# v6.net
KiCad netlist of a schematic drawn in EAGLE
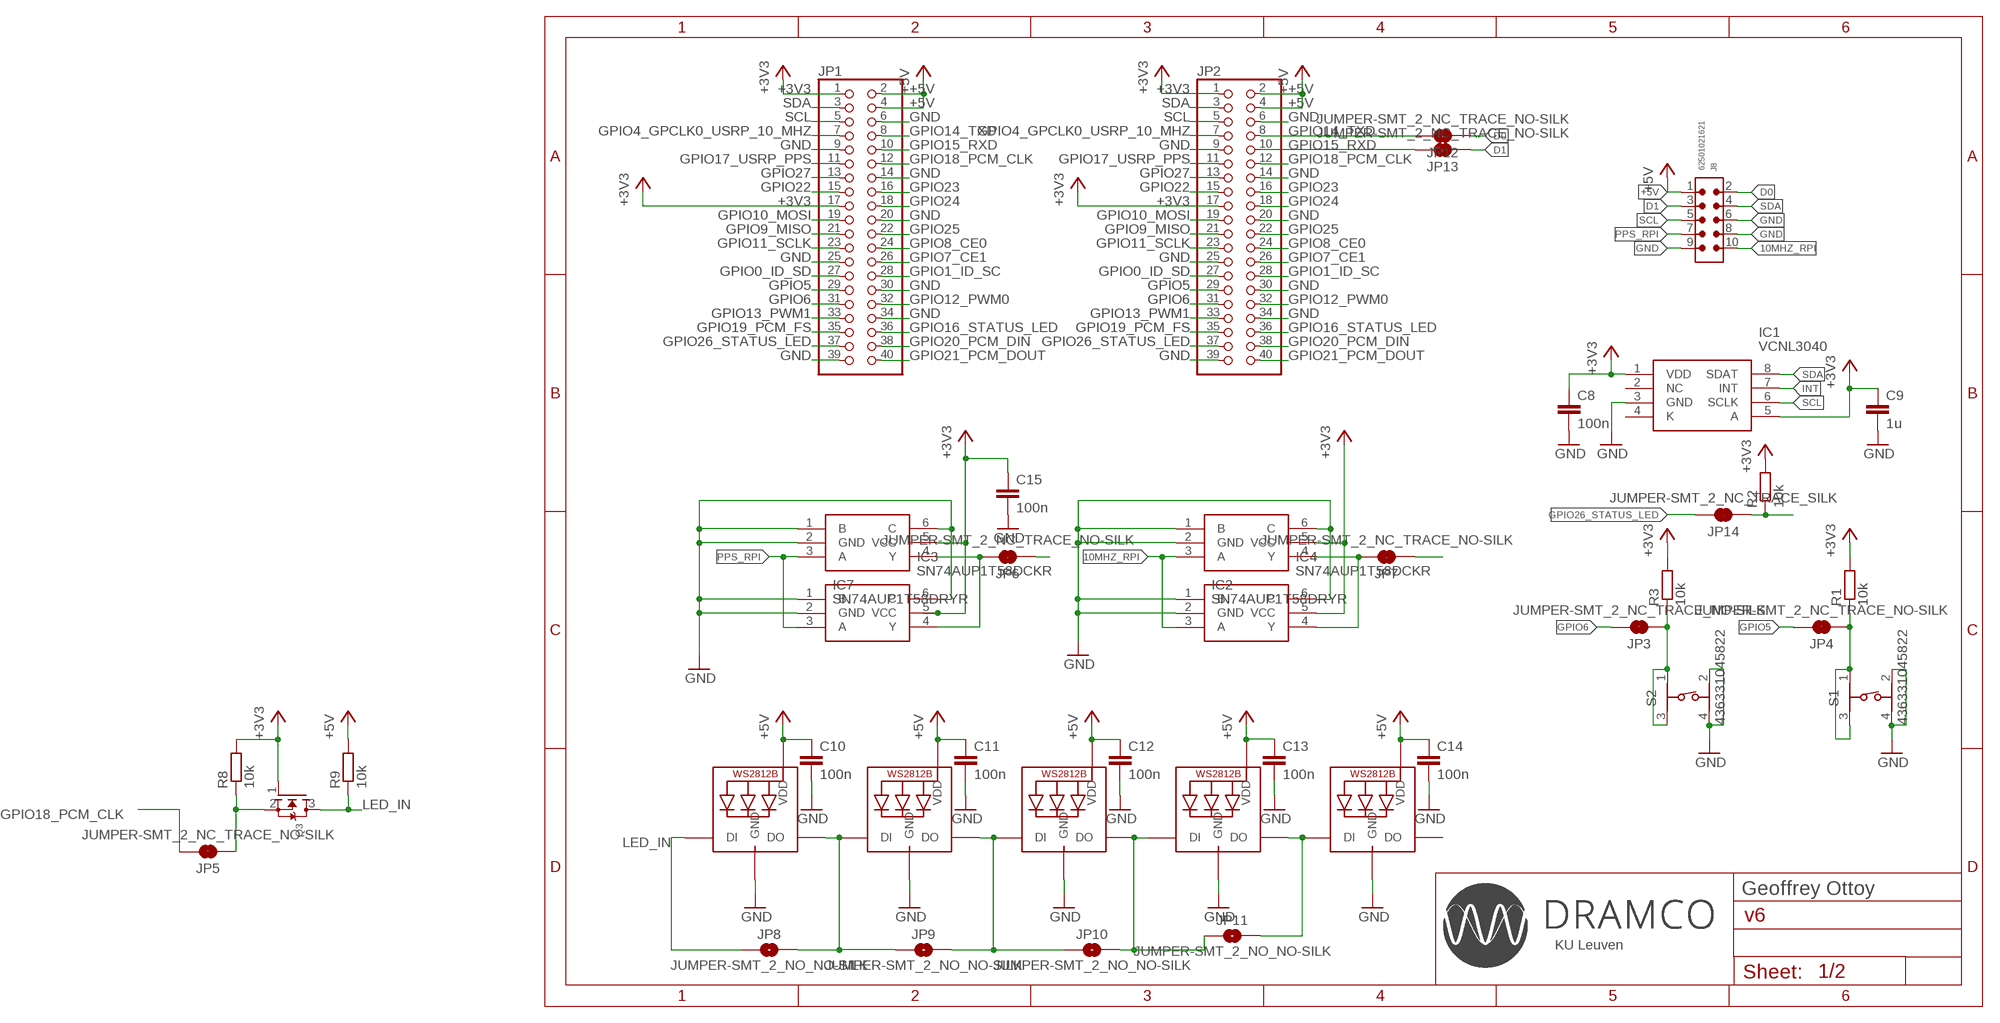
[diagram p0: schematic, sheet 1]
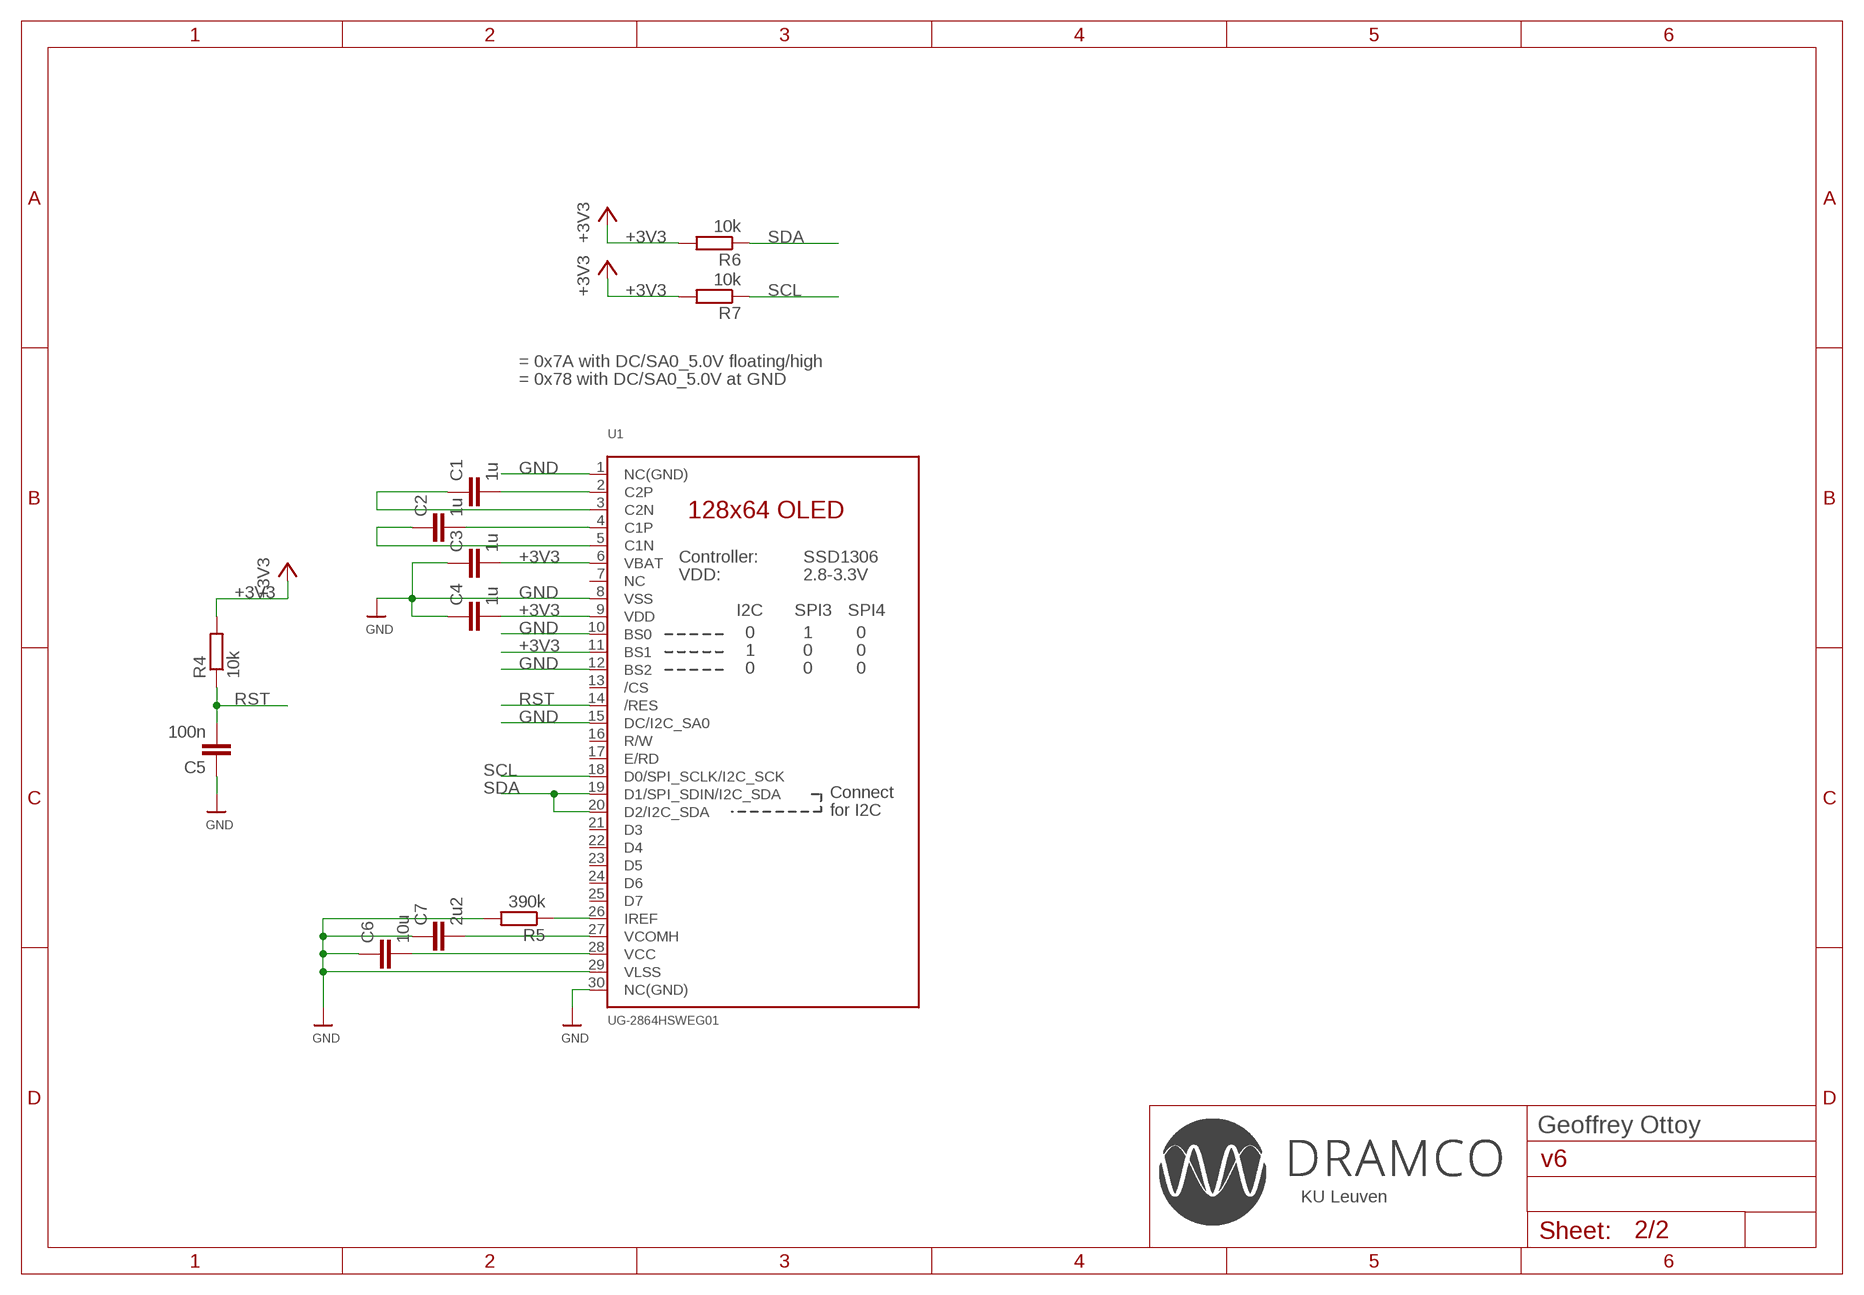
[diagram p1: schematic, sheet 2]

(export (version "E")
  (design (tool "Eeschema 10.0.6"))
  (components
    (comp (ref "C1")
      (value "1u")
      (footprint "eagle-import:C0603")
      (libsource (lib "eagle-import") (part "C-EUC0603"))
    )
    (comp (ref "C2")
      (value "1u")
      (footprint "eagle-import:C0603")
      (libsource (lib "eagle-import") (part "C-EUC0603"))
    )
    (comp (ref "C3")
      (value "1u")
      (footprint "eagle-import:C0603")
      (libsource (lib "eagle-import") (part "C-EUC0603"))
    )
    (comp (ref "C4")
      (value "1u")
      (footprint "eagle-import:C0603")
      (libsource (lib "eagle-import") (part "C-EUC0603"))
    )
    (comp (ref "C5")
      (value "100n")
      (footprint "eagle-import:C0603")
      (libsource (lib "eagle-import") (part "C-EUC0603"))
    )
    (comp (ref "C6")
      (value "10u")
      (footprint "eagle-import:C0603")
      (libsource (lib "eagle-import") (part "C-EUC0603"))
    )
    (comp (ref "C7")
      (value "2u2")
      (footprint "eagle-import:C0603")
      (libsource (lib "eagle-import") (part "C-EUC0603"))
    )
    (comp (ref "R4")
      (value "10k")
      (footprint "eagle-import:R0603")
      (libsource (lib "eagle-import") (part "R-EU_R0603"))
    )
    (comp (ref "R5")
      (value "390k")
      (footprint "eagle-import:R0603")
      (libsource (lib "eagle-import") (part "R-EU_R0603"))
    )
    (comp (ref "R6")
      (value "10k")
      (footprint "eagle-import:R0603")
      (libsource (lib "eagle-import") (part "R-EU_R0603"))
    )
    (comp (ref "R7")
      (value "10k")
      (footprint "eagle-import:R0603")
      (libsource (lib "eagle-import") (part "R-EU_R0603"))
    )
    (comp (ref "U1")
      (value "UG-2864HSWEG01")
      (footprint "eagle-import:UG-2864HSWEG01_0.96IN_WRAPAROUND")
      (libsource (lib "eagle-import") (part "DISP_OLED_UG-2864HSWEG010.96{dblquote}"))
    )
    (comp (ref "C8")
      (value "100n")
      (footprint "eagle-import:C0603")
      (libsource (lib "eagle-import") (part "C-EUC0603"))
    )
    (comp (ref "C9")
      (value "1u")
      (footprint "eagle-import:C0603")
      (libsource (lib "eagle-import") (part "C-EUC0603"))
    )
    (comp (ref "C10")
      (value "100n")
      (footprint "eagle-import:C0603")
      (libsource (lib "eagle-import") (part "C-EUC0603"))
    )
    (comp (ref "C11")
      (value "100n")
      (footprint "eagle-import:C0603")
      (libsource (lib "eagle-import") (part "C-EUC0603"))
    )
    (comp (ref "C12")
      (value "100n")
      (footprint "eagle-import:C0603")
      (libsource (lib "eagle-import") (part "C-EUC0603"))
    )
    (comp (ref "C13")
      (value "100n")
      (footprint "eagle-import:C0603")
      (libsource (lib "eagle-import") (part "C-EUC0603"))
    )
    (comp (ref "C14")
      (value "100n")
      (footprint "eagle-import:C0603")
      (libsource (lib "eagle-import") (part "C-EUC0603"))
    )
    (comp (ref "C15")
      (value "100n")
      (footprint "eagle-import:C0603")
      (libsource (lib "eagle-import") (part "C-EUC0603"))
    )
    (comp (ref "IC1")
      (value "VCNL3040")
      (footprint "eagle-import:SON108P200X400X115-8N")
      (fields (field (name "MOUSER_PART_NUMBER") "78-VCNL3040"))
      (libsource (lib "eagle-import") (part "VCNL3040"))
    )
    (comp (ref "IC2")
      (value "SN74AUP1T58DRYR")
      (footprint "eagle-import:SON50P100X145X60-6N")
      (libsource (lib "eagle-import") (part "SN74AUP1T58DRYR"))
    )
    (comp (ref "IC3")
      (value "SN74AUP1T58DCKR")
      (footprint "eagle-import:SOT65P210X110-6N")
      (libsource (lib "eagle-import") (part "SN74AUP1T58DCKR"))
    )
    (comp (ref "IC4")
      (value "SN74AUP1T58DCKR")
      (footprint "eagle-import:SOT65P210X110-6N")
      (libsource (lib "eagle-import") (part "SN74AUP1T58DCKR"))
    )
    (comp (ref "IC7")
      (value "SN74AUP1T58DRYR")
      (footprint "eagle-import:SON50P100X145X60-6N")
      (libsource (lib "eagle-import") (part "SN74AUP1T58DRYR"))
    )
    (comp (ref "J8")
      (value "62501021621")
      (footprint "eagle-import:62501021621")
      (libsource (lib "eagle-import") (part "6250XX21621_62501021621"))
    )
    (comp (ref "JP1")
      (value "PINHD-2X20")
      (footprint "eagle-import:2X20")
      (libsource (lib "eagle-import") (part "PINHD-2X20"))
    )
    (comp (ref "JP2")
      (value "PINHD-2X20/90")
      (footprint "eagle-import:2X20_90")
      (libsource (lib "eagle-import") (part "PINHD-2X20/90"))
    )
    (comp (ref "JP3")
      (value "JUMPER-SMT_2_NC_TRACE_NO-SILK")
      (footprint "eagle-import:SMT-JUMPER_2_NC_TRACE_NO-SILK")
      (libsource (lib "eagle-import") (part "JUMPER-SMT_2_NC_TRACE_NO-SILK"))
    )
    (comp (ref "JP4")
      (value "JUMPER-SMT_2_NC_TRACE_NO-SILK")
      (footprint "eagle-import:SMT-JUMPER_2_NC_TRACE_NO-SILK")
      (libsource (lib "eagle-import") (part "JUMPER-SMT_2_NC_TRACE_NO-SILK"))
    )
    (comp (ref "JP5")
      (value "JUMPER-SMT_2_NC_TRACE_NO-SILK")
      (footprint "eagle-import:SMT-JUMPER_2_NC_TRACE_NO-SILK")
      (libsource (lib "eagle-import") (part "JUMPER-SMT_2_NC_TRACE_NO-SILK"))
    )
    (comp (ref "JP6")
      (value "JUMPER-SMT_2_NC_TRACE_NO-SILK")
      (footprint "eagle-import:SMT-JUMPER_2_NC_TRACE_NO-SILK")
      (libsource (lib "eagle-import") (part "JUMPER-SMT_2_NC_TRACE_NO-SILK"))
    )
    (comp (ref "JP7")
      (value "JUMPER-SMT_2_NC_TRACE_NO-SILK")
      (footprint "eagle-import:SMT-JUMPER_2_NC_TRACE_NO-SILK")
      (libsource (lib "eagle-import") (part "JUMPER-SMT_2_NC_TRACE_NO-SILK"))
    )
    (comp (ref "JP8")
      (value "JUMPER-SMT_2_NO_NO-SILK")
      (footprint "eagle-import:SMT-JUMPER_2_NO_NO-SILK")
      (libsource (lib "eagle-import") (part "JUMPER-SMT_2_NO_NO-SILK"))
    )
    (comp (ref "JP9")
      (value "JUMPER-SMT_2_NO_NO-SILK")
      (footprint "eagle-import:SMT-JUMPER_2_NO_NO-SILK")
      (libsource (lib "eagle-import") (part "JUMPER-SMT_2_NO_NO-SILK"))
    )
    (comp (ref "JP10")
      (value "JUMPER-SMT_2_NO_NO-SILK")
      (footprint "eagle-import:SMT-JUMPER_2_NO_NO-SILK")
      (libsource (lib "eagle-import") (part "JUMPER-SMT_2_NO_NO-SILK"))
    )
    (comp (ref "JP11")
      (value "JUMPER-SMT_2_NO_NO-SILK")
      (footprint "eagle-import:SMT-JUMPER_2_NO_NO-SILK")
      (libsource (lib "eagle-import") (part "JUMPER-SMT_2_NO_NO-SILK"))
    )
    (comp (ref "JP12")
      (value "JUMPER-SMT_2_NC_TRACE_NO-SILK")
      (footprint "eagle-import:SMT-JUMPER_2_NC_TRACE_NO-SILK")
      (libsource (lib "eagle-import") (part "JUMPER-SMT_2_NC_TRACE_NO-SILK"))
    )
    (comp (ref "JP13")
      (value "JUMPER-SMT_2_NC_TRACE_NO-SILK")
      (footprint "eagle-import:SMT-JUMPER_2_NC_TRACE_NO-SILK")
      (libsource (lib "eagle-import") (part "JUMPER-SMT_2_NC_TRACE_NO-SILK"))
    )
    (comp (ref "JP14")
      (value "JUMPER-SMT_2_NC_TRACE_SILK")
      (footprint "eagle-import:SMT-JUMPER_2_NC_TRACE_SILK")
      (libsource (lib "eagle-import") (part "JUMPER-SMT_2_NC_TRACE_SILK"))
    )
    (comp (ref "LED1")
      (value "WS2812B5050")
      (footprint "eagle-import:WS2812B")
      (libsource (lib "eagle-import") (part "WS2812B5050"))
    )
    (comp (ref "LED2")
      (value "WS2812B5050")
      (footprint "eagle-import:WS2812B")
      (libsource (lib "eagle-import") (part "WS2812B5050"))
    )
    (comp (ref "LED3")
      (value "WS2812B5050")
      (footprint "eagle-import:WS2812B")
      (libsource (lib "eagle-import") (part "WS2812B5050"))
    )
    (comp (ref "LED4")
      (value "WS2812B5050")
      (footprint "eagle-import:WS2812B")
      (libsource (lib "eagle-import") (part "WS2812B5050"))
    )
    (comp (ref "LED5")
      (value "WS2812B5050")
      (footprint "eagle-import:WS2812B")
      (libsource (lib "eagle-import") (part "WS2812B5050"))
    )
    (comp (ref "Q3")
      (value "MOSFET-NREFLOW")
      (footprint "eagle-import:SOT23")
      (libsource (lib "eagle-import") (part "MOSFET-NREFLOW"))
    )
    (comp (ref "R1")
      (value "10k")
      (footprint "eagle-import:R0603")
      (libsource (lib "eagle-import") (part "R-EU_R0603"))
    )
    (comp (ref "R2")
      (value "10k")
      (footprint "eagle-import:R0603")
      (libsource (lib "eagle-import") (part "R-EU_R0603"))
    )
    (comp (ref "R3")
      (value "10k")
      (footprint "eagle-import:R0603")
      (libsource (lib "eagle-import") (part "R-EU_R0603"))
    )
    (comp (ref "R8")
      (value "10k")
      (footprint "eagle-import:R0603")
      (libsource (lib "eagle-import") (part "R-EU_R0603"))
    )
    (comp (ref "R9")
      (value "10k")
      (footprint "eagle-import:R0603")
      (libsource (lib "eagle-import") (part "R-EU_R0603"))
    )
    (comp (ref "S1")
      (value "436331045822")
      (footprint "eagle-import:4363X10458XX")
      (libsource (lib "eagle-import") (part "436331045822"))
    )
    (comp (ref "S2")
      (value "436331045822")
      (footprint "eagle-import:4363X10458XX")
      (libsource (lib "eagle-import") (part "436331045822"))
    )
  )
  (nets
    (net (code "1") (name "+3V3") (class "Default")
      (node (ref "C15") (pin "1") (pinfunction "1_1") (pintype "passive"))
      (node (ref "C3") (pin "2") (pinfunction "2_2") (pintype "passive"))
      (node (ref "C4") (pin "2") (pinfunction "2_2") (pintype "passive"))
      (node (ref "C8") (pin "1") (pinfunction "1_1") (pintype "passive"))
      (node (ref "C9") (pin "1") (pinfunction "1_1") (pintype "passive"))
      (node (ref "IC1") (pin "1") (pinfunction "VDD_1") (pintype "bidirectional"))
      (node (ref "IC1") (pin "5") (pinfunction "A_5") (pintype "bidirectional"))
      (node (ref "IC2") (pin "5") (pinfunction "VCC_5") (pintype "bidirectional"))
      (node (ref "IC3") (pin "5") (pinfunction "VCC_5") (pintype "bidirectional"))
      (node (ref "IC4") (pin "5") (pinfunction "VCC_5") (pintype "bidirectional"))
      (node (ref "IC7") (pin "5") (pinfunction "VCC_5") (pintype "bidirectional"))
      (node (ref "JP1") (pin "1") (pinfunction "1_1") (pintype "passive"))
      (node (ref "JP1") (pin "17") (pinfunction "17_17") (pintype "passive"))
      (node (ref "JP2") (pin "1") (pinfunction "1_1") (pintype "passive"))
      (node (ref "JP2") (pin "17") (pinfunction "17_17") (pintype "passive"))
      (node (ref "Q3") (pin "1") (pinfunction "G_1") (pintype "bidirectional"))
      (node (ref "R1") (pin "2") (pinfunction "2_2") (pintype "passive"))
      (node (ref "R2") (pin "2") (pinfunction "2_2") (pintype "passive"))
      (node (ref "R3") (pin "2") (pinfunction "2_2") (pintype "passive"))
      (node (ref "R4") (pin "2") (pinfunction "2_2") (pintype "passive"))
      (node (ref "R6") (pin "2") (pinfunction "2_2") (pintype "passive"))
      (node (ref "R7") (pin "2") (pinfunction "2_2") (pintype "passive"))
      (node (ref "R8") (pin "2") (pinfunction "2_2") (pintype "passive"))
      (node (ref "U1") (pin "11") (pinfunction "BS1_11") (pintype "input"))
      (node (ref "U1") (pin "6") (pinfunction "VBAT_6") (pintype "input"))
      (node (ref "U1") (pin "9") (pinfunction "VDD_9") (pintype "power_in"))
    )
    (net (code "2") (name "+5V") (class "Default")
      (node (ref "C10") (pin "1") (pinfunction "1_1") (pintype "passive"))
      (node (ref "C11") (pin "1") (pinfunction "1_1") (pintype "passive"))
      (node (ref "C12") (pin "1") (pinfunction "1_1") (pintype "passive"))
      (node (ref "C13") (pin "1") (pinfunction "1_1") (pintype "passive"))
      (node (ref "C14") (pin "1") (pinfunction "1_1") (pintype "passive"))
      (node (ref "J8") (pin "1") (pinfunction "1_1") (pintype "passive"))
      (node (ref "JP1") (pin "2") (pinfunction "2_2") (pintype "passive"))
      (node (ref "JP1") (pin "4") (pinfunction "4_4") (pintype "passive"))
      (node (ref "JP2") (pin "2") (pinfunction "2_2") (pintype "passive"))
      (node (ref "JP2") (pin "4") (pinfunction "4_4") (pintype "passive"))
      (node (ref "LED1") (pin "1-VDD") (pinfunction "VDD_1-VDD") (pintype "power_in"))
      (node (ref "LED2") (pin "1-VDD") (pinfunction "VDD_1-VDD") (pintype "power_in"))
      (node (ref "LED3") (pin "1-VDD") (pinfunction "VDD_1-VDD") (pintype "power_in"))
      (node (ref "LED4") (pin "1-VDD") (pinfunction "VDD_1-VDD") (pintype "power_in"))
      (node (ref "LED5") (pin "1-VDD") (pinfunction "VDD_1-VDD") (pintype "power_in"))
      (node (ref "R9") (pin "2") (pinfunction "2_2") (pintype "passive"))
    )
    (net (code "3") (name "10MHZ_RPI") (class "Default")
      (node (ref "IC2") (pin "3") (pinfunction "A_3") (pintype "bidirectional"))
      (node (ref "IC4") (pin "3") (pinfunction "A_3") (pintype "bidirectional"))
      (node (ref "J8") (pin "10") (pinfunction "10_10") (pintype "passive"))
    )
    (net (code "4") (name "D0") (class "Default")
      (node (ref "J8") (pin "2") (pinfunction "2_2") (pintype "passive"))
      (node (ref "JP12") (pin "1") (pinfunction "1_1") (pintype "passive"))
    )
    (net (code "5") (name "D1") (class "Default")
      (node (ref "J8") (pin "3") (pinfunction "3_3") (pintype "passive"))
      (node (ref "JP13") (pin "1") (pinfunction "1_1") (pintype "passive"))
    )
    (net (code "6") (name "GND") (class "Default")
      (node (ref "C10") (pin "2") (pinfunction "2_2") (pintype "passive"))
      (node (ref "C11") (pin "2") (pinfunction "2_2") (pintype "passive"))
      (node (ref "C12") (pin "2") (pinfunction "2_2") (pintype "passive"))
      (node (ref "C13") (pin "2") (pinfunction "2_2") (pintype "passive"))
      (node (ref "C14") (pin "2") (pinfunction "2_2") (pintype "passive"))
      (node (ref "C15") (pin "2") (pinfunction "2_2") (pintype "passive"))
      (node (ref "C3") (pin "1") (pinfunction "1_1") (pintype "passive"))
      (node (ref "C4") (pin "1") (pinfunction "1_1") (pintype "passive"))
      (node (ref "C5") (pin "1") (pinfunction "1_1") (pintype "passive"))
      (node (ref "C6") (pin "1") (pinfunction "1_1") (pintype "passive"))
      (node (ref "C7") (pin "1") (pinfunction "1_1") (pintype "passive"))
      (node (ref "C8") (pin "2") (pinfunction "2_2") (pintype "passive"))
      (node (ref "C9") (pin "2") (pinfunction "2_2") (pintype "passive"))
      (node (ref "IC1") (pin "3") (pinfunction "GND_3") (pintype "bidirectional"))
      (node (ref "IC2") (pin "1") (pinfunction "B_1") (pintype "bidirectional"))
      (node (ref "IC2") (pin "2") (pinfunction "GND_2") (pintype "bidirectional"))
      (node (ref "IC2") (pin "6") (pinfunction "C_6") (pintype "bidirectional"))
      (node (ref "IC3") (pin "1") (pinfunction "B_1") (pintype "bidirectional"))
      (node (ref "IC3") (pin "2") (pinfunction "GND_2") (pintype "bidirectional"))
      (node (ref "IC3") (pin "6") (pinfunction "C_6") (pintype "bidirectional"))
      (node (ref "IC4") (pin "1") (pinfunction "B_1") (pintype "bidirectional"))
      (node (ref "IC4") (pin "2") (pinfunction "GND_2") (pintype "bidirectional"))
      (node (ref "IC4") (pin "6") (pinfunction "C_6") (pintype "bidirectional"))
      (node (ref "IC7") (pin "1") (pinfunction "B_1") (pintype "bidirectional"))
      (node (ref "IC7") (pin "2") (pinfunction "GND_2") (pintype "bidirectional"))
      (node (ref "IC7") (pin "6") (pinfunction "C_6") (pintype "bidirectional"))
      (node (ref "J8") (pin "6") (pinfunction "6_6") (pintype "passive"))
      (node (ref "J8") (pin "8") (pinfunction "8_8") (pintype "passive"))
      (node (ref "J8") (pin "9") (pinfunction "9_9") (pintype "passive"))
      (node (ref "JP1") (pin "14") (pinfunction "14_14") (pintype "passive"))
      (node (ref "JP1") (pin "20") (pinfunction "20_20") (pintype "passive"))
      (node (ref "JP1") (pin "25") (pinfunction "25_25") (pintype "passive"))
      (node (ref "JP1") (pin "30") (pinfunction "30_30") (pintype "passive"))
      (node (ref "JP1") (pin "34") (pinfunction "34_34") (pintype "passive"))
      (node (ref "JP1") (pin "39") (pinfunction "39_39") (pintype "passive"))
      (node (ref "JP1") (pin "6") (pinfunction "6_6") (pintype "passive"))
      (node (ref "JP1") (pin "9") (pinfunction "9_9") (pintype "passive"))
      (node (ref "JP2") (pin "14") (pinfunction "14_14") (pintype "passive"))
      (node (ref "JP2") (pin "20") (pinfunction "20_20") (pintype "passive"))
      (node (ref "JP2") (pin "25") (pinfunction "25_25") (pintype "passive"))
      (node (ref "JP2") (pin "30") (pinfunction "30_30") (pintype "passive"))
      (node (ref "JP2") (pin "34") (pinfunction "34_34") (pintype "passive"))
      (node (ref "JP2") (pin "39") (pinfunction "39_39") (pintype "passive"))
      (node (ref "JP2") (pin "6") (pinfunction "6_6") (pintype "passive"))
      (node (ref "JP2") (pin "9") (pinfunction "9_9") (pintype "passive"))
      (node (ref "LED1") (pin "3-GND") (pinfunction "GND_3-GND") (pintype "power_in"))
      (node (ref "LED2") (pin "3-GND") (pinfunction "GND_3-GND") (pintype "power_in"))
      (node (ref "LED3") (pin "3-GND") (pinfunction "GND_3-GND") (pintype "power_in"))
      (node (ref "LED4") (pin "3-GND") (pinfunction "GND_3-GND") (pintype "power_in"))
      (node (ref "LED5") (pin "3-GND") (pinfunction "GND_3-GND") (pintype "power_in"))
      (node (ref "R5") (pin "2") (pinfunction "2_2") (pintype "passive"))
      (node (ref "S1") (pin "2") (pinfunction "4_2") (pintype "passive"))
      (node (ref "S1") (pin "4") (pinfunction "2_4") (pintype "passive"))
      (node (ref "S2") (pin "2") (pinfunction "4_2") (pintype "passive"))
      (node (ref "S2") (pin "4") (pinfunction "2_4") (pintype "passive"))
      (node (ref "U1") (pin "1") (pinfunction "NC(GND)_1") (pintype "input"))
      (node (ref "U1") (pin "10") (pinfunction "BS0_10") (pintype "input"))
      (node (ref "U1") (pin "12") (pinfunction "BS2_12") (pintype "input"))
      (node (ref "U1") (pin "15") (pinfunction "DC/I2C_SA0_15") (pintype "input"))
      (node (ref "U1") (pin "29") (pinfunction "VLSS_29") (pintype "power_in"))
      (node (ref "U1") (pin "30") (pinfunction "NC(GND)_30") (pintype "input"))
      (node (ref "U1") (pin "8") (pinfunction "VSS_8") (pintype "power_in"))
    )
    (net (code "7") (name "GPIO0_ID_SD") (class "Default")
      (node (ref "JP1") (pin "27") (pinfunction "27_27") (pintype "passive"))
      (node (ref "JP2") (pin "27") (pinfunction "27_27") (pintype "passive"))
    )
    (net (code "8") (name "GPIO1_ID_SC") (class "Default")
      (node (ref "JP1") (pin "28") (pinfunction "28_28") (pintype "passive"))
      (node (ref "JP2") (pin "28") (pinfunction "28_28") (pintype "passive"))
    )
    (net (code "9") (name "GPIO4_GPCLK0_USRP_10_MHZ") (class "Default")
      (node (ref "JP1") (pin "7") (pinfunction "7_7") (pintype "passive"))
      (node (ref "JP2") (pin "7") (pinfunction "7_7") (pintype "passive"))
      (node (ref "JP7") (pin "1") (pinfunction "1_1") (pintype "passive"))
    )
    (net (code "10") (name "GPIO5") (class "Default")
      (node (ref "JP1") (pin "29") (pinfunction "29_29") (pintype "passive"))
      (node (ref "JP2") (pin "29") (pinfunction "29_29") (pintype "passive"))
      (node (ref "JP4") (pin "2") (pinfunction "2_2") (pintype "passive"))
    )
    (net (code "11") (name "GPIO6") (class "Default")
      (node (ref "JP1") (pin "31") (pinfunction "31_31") (pintype "passive"))
      (node (ref "JP2") (pin "31") (pinfunction "31_31") (pintype "passive"))
      (node (ref "JP3") (pin "2") (pinfunction "2_2") (pintype "passive"))
    )
    (net (code "12") (name "GPIO7_CE1") (class "Default")
      (node (ref "JP1") (pin "26") (pinfunction "26_26") (pintype "passive"))
      (node (ref "JP2") (pin "26") (pinfunction "26_26") (pintype "passive"))
    )
    (net (code "13") (name "GPIO8_CE0") (class "Default")
      (node (ref "JP1") (pin "24") (pinfunction "24_24") (pintype "passive"))
      (node (ref "JP2") (pin "24") (pinfunction "24_24") (pintype "passive"))
    )
    (net (code "14") (name "GPIO9_MISO") (class "Default")
      (node (ref "JP1") (pin "21") (pinfunction "21_21") (pintype "passive"))
      (node (ref "JP2") (pin "21") (pinfunction "21_21") (pintype "passive"))
    )
    (net (code "15") (name "GPIO10_MOSI") (class "Default")
      (node (ref "JP1") (pin "19") (pinfunction "19_19") (pintype "passive"))
      (node (ref "JP2") (pin "19") (pinfunction "19_19") (pintype "passive"))
    )
    (net (code "16") (name "GPIO11_SCLK") (class "Default")
      (node (ref "JP1") (pin "23") (pinfunction "23_23") (pintype "passive"))
      (node (ref "JP2") (pin "23") (pinfunction "23_23") (pintype "passive"))
    )
    (net (code "17") (name "GPIO12_PWM0") (class "Default")
      (node (ref "JP1") (pin "32") (pinfunction "32_32") (pintype "passive"))
      (node (ref "JP2") (pin "32") (pinfunction "32_32") (pintype "passive"))
    )
    (net (code "18") (name "GPIO13_PWM1") (class "Default")
      (node (ref "JP1") (pin "33") (pinfunction "33_33") (pintype "passive"))
      (node (ref "JP2") (pin "33") (pinfunction "33_33") (pintype "passive"))
    )
    (net (code "19") (name "GPIO14_TXD") (class "Default")
      (node (ref "JP1") (pin "8") (pinfunction "8_8") (pintype "passive"))
      (node (ref "JP12") (pin "2") (pinfunction "2_2") (pintype "passive"))
      (node (ref "JP2") (pin "8") (pinfunction "8_8") (pintype "passive"))
    )
    (net (code "20") (name "GPIO15_RXD") (class "Default")
      (node (ref "JP1") (pin "10") (pinfunction "10_10") (pintype "passive"))
      (node (ref "JP13") (pin "2") (pinfunction "2_2") (pintype "passive"))
      (node (ref "JP2") (pin "10") (pinfunction "10_10") (pintype "passive"))
    )
    (net (code "21") (name "GPIO16_STATUS_LED") (class "Default")
      (node (ref "JP1") (pin "36") (pinfunction "36_36") (pintype "passive"))
      (node (ref "JP2") (pin "36") (pinfunction "36_36") (pintype "passive"))
    )
    (net (code "22") (name "GPIO17_USRP_PPS") (class "Default")
      (node (ref "JP1") (pin "11") (pinfunction "11_11") (pintype "passive"))
      (node (ref "JP2") (pin "11") (pinfunction "11_11") (pintype "passive"))
      (node (ref "JP6") (pin "1") (pinfunction "1_1") (pintype "passive"))
    )
    (net (code "23") (name "GPIO18_PCM_CLK") (class "Default")
      (node (ref "JP1") (pin "12") (pinfunction "12_12") (pintype "passive"))
      (node (ref "JP2") (pin "12") (pinfunction "12_12") (pintype "passive"))
      (node (ref "JP5") (pin "2") (pinfunction "2_2") (pintype "passive"))
    )
    (net (code "24") (name "GPIO19_PCM_FS") (class "Default")
      (node (ref "JP1") (pin "35") (pinfunction "35_35") (pintype "passive"))
      (node (ref "JP2") (pin "35") (pinfunction "35_35") (pintype "passive"))
    )
    (net (code "25") (name "GPIO20_PCM_DIN") (class "Default")
      (node (ref "JP1") (pin "38") (pinfunction "38_38") (pintype "passive"))
      (node (ref "JP2") (pin "38") (pinfunction "38_38") (pintype "passive"))
    )
    (net (code "26") (name "GPIO21_PCM_DOUT") (class "Default")
      (node (ref "JP1") (pin "40") (pinfunction "40_40") (pintype "passive"))
      (node (ref "JP2") (pin "40") (pinfunction "40_40") (pintype "passive"))
    )
    (net (code "27") (name "GPIO22") (class "Default")
      (node (ref "JP1") (pin "15") (pinfunction "15_15") (pintype "passive"))
      (node (ref "JP2") (pin "15") (pinfunction "15_15") (pintype "passive"))
    )
    (net (code "28") (name "GPIO23") (class "Default")
      (node (ref "JP1") (pin "16") (pinfunction "16_16") (pintype "passive"))
      (node (ref "JP2") (pin "16") (pinfunction "16_16") (pintype "passive"))
    )
    (net (code "29") (name "GPIO24") (class "Default")
      (node (ref "JP1") (pin "18") (pinfunction "18_18") (pintype "passive"))
      (node (ref "JP2") (pin "18") (pinfunction "18_18") (pintype "passive"))
    )
    (net (code "30") (name "GPIO25") (class "Default")
      (node (ref "JP1") (pin "22") (pinfunction "22_22") (pintype "passive"))
      (node (ref "JP2") (pin "22") (pinfunction "22_22") (pintype "passive"))
    )
    (net (code "31") (name "GPIO26_STATUS_LED") (class "Default")
      (node (ref "JP1") (pin "37") (pinfunction "37_37") (pintype "passive"))
      (node (ref "JP14") (pin "2") (pinfunction "2_2") (pintype "passive"))
      (node (ref "JP2") (pin "37") (pinfunction "37_37") (pintype "passive"))
    )
    (net (code "32") (name "GPIO27") (class "Default")
      (node (ref "JP1") (pin "13") (pinfunction "13_13") (pintype "passive"))
      (node (ref "JP2") (pin "13") (pinfunction "13_13") (pintype "passive"))
    )
    (net (code "33") (name "INT") (class "Default")
      (node (ref "IC1") (pin "7") (pinfunction "INT_7") (pintype "bidirectional"))
      (node (ref "JP14") (pin "1") (pinfunction "1_1") (pintype "passive"))
      (node (ref "R2") (pin "1") (pinfunction "1_1") (pintype "passive"))
    )
    (net (code "34") (name "LED_IN") (class "Default")
      (node (ref "JP8") (pin "1") (pinfunction "1_1") (pintype "passive"))
      (node (ref "LED1") (pin "4-DIN") (pinfunction "DI_4-DIN") (pintype "input"))
      (node (ref "Q3") (pin "3") (pinfunction "D_3") (pintype "bidirectional"))
      (node (ref "R9") (pin "1") (pinfunction "1_1") (pintype "passive"))
    )
    (net (code "35") (name "Net-(IC2-Y)") (class "Default")
      (node (ref "IC2") (pin "4") (pinfunction "Y_4") (pintype "bidirectional"))
      (node (ref "IC4") (pin "4") (pinfunction "Y_4") (pintype "bidirectional"))
      (node (ref "JP7") (pin "2") (pinfunction "2_2") (pintype "passive"))
    )
    (net (code "36") (name "Net-(IC3-Y)") (class "Default")
      (node (ref "IC3") (pin "4") (pinfunction "Y_4") (pintype "bidirectional"))
      (node (ref "IC7") (pin "4") (pinfunction "Y_4") (pintype "bidirectional"))
      (node (ref "JP6") (pin "2") (pinfunction "2_2") (pintype "passive"))
    )
    (net (code "37") (name "Net-(LED1-DO)") (class "Default")
      (node (ref "JP8") (pin "2") (pinfunction "2_2") (pintype "passive"))
      (node (ref "JP9") (pin "1") (pinfunction "1_1") (pintype "passive"))
      (node (ref "LED1") (pin "2-DOUT") (pinfunction "DO_2-DOUT") (pintype "output"))
      (node (ref "LED2") (pin "4-DIN") (pinfunction "DI_4-DIN") (pintype "input"))
    )
    (net (code "38") (name "Net-(LED2-DO)") (class "Default")
      (node (ref "JP10") (pin "1") (pinfunction "1_1") (pintype "passive"))
      (node (ref "JP9") (pin "2") (pinfunction "2_2") (pintype "passive"))
      (node (ref "LED2") (pin "2-DOUT") (pinfunction "DO_2-DOUT") (pintype "output"))
      (node (ref "LED3") (pin "4-DIN") (pinfunction "DI_4-DIN") (pintype "input"))
    )
    (net (code "39") (name "Net-(LED3-DO)") (class "Default")
      (node (ref "JP10") (pin "2") (pinfunction "2_2") (pintype "passive"))
      (node (ref "JP11") (pin "1") (pinfunction "1_1") (pintype "passive"))
      (node (ref "LED3") (pin "2-DOUT") (pinfunction "DO_2-DOUT") (pintype "output"))
      (node (ref "LED4") (pin "4-DIN") (pinfunction "DI_4-DIN") (pintype "input"))
    )
    (net (code "40") (name "Net-(LED4-DO)") (class "Default")
      (node (ref "JP11") (pin "2") (pinfunction "2_2") (pintype "passive"))
      (node (ref "LED4") (pin "2-DOUT") (pinfunction "DO_2-DOUT") (pintype "output"))
      (node (ref "LED5") (pin "4-DIN") (pinfunction "DI_4-DIN") (pintype "input"))
    )
    (net (code "41") (name "Net-(Q3-S)") (class "Default")
      (node (ref "JP5") (pin "1") (pinfunction "1_1") (pintype "passive"))
      (node (ref "Q3") (pin "2") (pinfunction "S_2") (pintype "bidirectional"))
      (node (ref "R8") (pin "1") (pinfunction "1_1") (pintype "passive"))
    )
    (net (code "42") (name "Net-(S1-1)") (class "Default")
      (node (ref "JP4") (pin "1") (pinfunction "1_1") (pintype "passive"))
      (node (ref "R1") (pin "1") (pinfunction "1_1") (pintype "passive"))
      (node (ref "S1") (pin "1") (pinfunction "3_1") (pintype "passive"))
      (node (ref "S1") (pin "3") (pinfunction "1_3") (pintype "passive"))
    )
    (net (code "43") (name "Net-(S2-1)") (class "Default")
      (node (ref "JP3") (pin "1") (pinfunction "1_1") (pintype "passive"))
      (node (ref "R3") (pin "1") (pinfunction "1_1") (pintype "passive"))
      (node (ref "S2") (pin "1") (pinfunction "3_1") (pintype "passive"))
      (node (ref "S2") (pin "3") (pinfunction "1_3") (pintype "passive"))
    )
    (net (code "44") (name "Net-(U1-C1N)") (class "Default")
      (node (ref "C2") (pin "1") (pinfunction "1_1") (pintype "passive"))
      (node (ref "U1") (pin "5") (pinfunction "C1N_5") (pintype "input"))
    )
    (net (code "45") (name "Net-(U1-C1P)") (class "Default")
      (node (ref "C2") (pin "2") (pinfunction "2_2") (pintype "passive"))
      (node (ref "U1") (pin "4") (pinfunction "C1P_4") (pintype "input"))
    )
    (net (code "46") (name "Net-(U1-C2N)") (class "Default")
      (node (ref "C1") (pin "1") (pinfunction "1_1") (pintype "passive"))
      (node (ref "U1") (pin "3") (pinfunction "C2N_3") (pintype "input"))
    )
    (net (code "47") (name "Net-(U1-C2P)") (class "Default")
      (node (ref "C1") (pin "2") (pinfunction "2_2") (pintype "passive"))
      (node (ref "U1") (pin "2") (pinfunction "C2P_2") (pintype "input"))
    )
    (net (code "48") (name "Net-(U1-IREF)") (class "Default")
      (node (ref "R5") (pin "1") (pinfunction "1_1") (pintype "passive"))
      (node (ref "U1") (pin "26") (pinfunction "IREF_26") (pintype "input"))
    )
    (net (code "49") (name "Net-(U1-VCC)") (class "Default")
      (node (ref "C6") (pin "2") (pinfunction "2_2") (pintype "passive"))
      (node (ref "U1") (pin "28") (pinfunction "VCC_28") (pintype "power_in"))
    )
    (net (code "50") (name "Net-(U1-VCOMH)") (class "Default")
      (node (ref "C7") (pin "2") (pinfunction "2_2") (pintype "passive"))
      (node (ref "U1") (pin "27") (pinfunction "VCOMH_27") (pintype "output"))
    )
    (net (code "51") (name "PPS_RPI") (class "Default")
      (node (ref "IC3") (pin "3") (pinfunction "A_3") (pintype "bidirectional"))
      (node (ref "IC7") (pin "3") (pinfunction "A_3") (pintype "bidirectional"))
      (node (ref "J8") (pin "7") (pinfunction "7_7") (pintype "passive"))
    )
    (net (code "52") (name "RST") (class "Default")
      (node (ref "C5") (pin "2") (pinfunction "2_2") (pintype "passive"))
      (node (ref "R4") (pin "1") (pinfunction "1_1") (pintype "passive"))
      (node (ref "U1") (pin "14") (pinfunction "/RES_14") (pintype "input"))
    )
    (net (code "53") (name "SCL") (class "Default")
      (node (ref "IC1") (pin "6") (pinfunction "SCLK_6") (pintype "bidirectional"))
      (node (ref "J8") (pin "5") (pinfunction "5_5") (pintype "passive"))
      (node (ref "JP1") (pin "5") (pinfunction "5_5") (pintype "passive"))
      (node (ref "JP2") (pin "5") (pinfunction "5_5") (pintype "passive"))
      (node (ref "R7") (pin "1") (pinfunction "1_1") (pintype "passive"))
      (node (ref "U1") (pin "18") (pinfunction "D0/SPI_SCLK/I2C_SCK_18") (pintype "bidirectional"))
    )
    (net (code "54") (name "SDA") (class "Default")
      (node (ref "IC1") (pin "8") (pinfunction "SDAT_8") (pintype "bidirectional"))
      (node (ref "J8") (pin "4") (pinfunction "4_4") (pintype "passive"))
      (node (ref "JP1") (pin "3") (pinfunction "3_3") (pintype "passive"))
      (node (ref "JP2") (pin "3") (pinfunction "3_3") (pintype "passive"))
      (node (ref "R6") (pin "1") (pinfunction "1_1") (pintype "passive"))
      (node (ref "U1") (pin "19") (pinfunction "D1/SPI_SDIN/I2C_SDA_19") (pintype "bidirectional"))
      (node (ref "U1") (pin "20") (pinfunction "D2/I2C_SDA_20") (pintype "bidirectional"))
    )
    (net (code "55") (name "unconnected-(IC1-K-Pad4)") (class "Default")
      (node (ref "IC1") (pin "4") (pinfunction "K_4") (pintype "bidirectional"))
    )
    (net (code "56") (name "unconnected-(IC1-NC-Pad2)") (class "Default")
      (node (ref "IC1") (pin "2") (pinfunction "NC_2") (pintype "no_connect"))
    )
    (net (code "57") (name "unconnected-(LED5-DO-Pad2-DOUT)") (class "Default")
      (node (ref "LED5") (pin "2-DOUT") (pinfunction "DO_2-DOUT") (pintype "output"))
    )
    (net (code "58") (name "unconnected-(U1-D3-Pad21)") (class "Default")
      (node (ref "U1") (pin "21") (pinfunction "D3_21") (pintype "bidirectional"))
    )
    (net (code "59") (name "unconnected-(U1-D4-Pad22)") (class "Default")
      (node (ref "U1") (pin "22") (pinfunction "D4_22") (pintype "bidirectional"))
    )
    (net (code "60") (name "unconnected-(U1-D5-Pad23)") (class "Default")
      (node (ref "U1") (pin "23") (pinfunction "D5_23") (pintype "bidirectional"))
    )
    (net (code "61") (name "unconnected-(U1-D6-Pad24)") (class "Default")
      (node (ref "U1") (pin "24") (pinfunction "D6_24") (pintype "bidirectional"))
    )
    (net (code "62") (name "unconnected-(U1-D7-Pad25)") (class "Default")
      (node (ref "U1") (pin "25") (pinfunction "D7_25") (pintype "bidirectional"))
    )
    (net (code "63") (name "unconnected-(U1-E{slash}RD-Pad17)") (class "Default")
      (node (ref "U1") (pin "17") (pinfunction "E/RD_17") (pintype "input"))
    )
    (net (code "64") (name "unconnected-(U1-NC-Pad7)") (class "Default")
      (node (ref "U1") (pin "7") (pinfunction "NC_7") (pintype "no_connect"))
    )
    (net (code "65") (name "unconnected-(U1-R{slash}W-Pad16)") (class "Default")
      (node (ref "U1") (pin "16") (pinfunction "R/W_16") (pintype "input"))
    )
    (net (code "66") (name "unconnected-(U1-{slash}CS-Pad13)") (class "Default")
      (node (ref "U1") (pin "13") (pinfunction "/CS_13") (pintype "input"))
    )
  )
)
